# Display.net
KiCad netlist of a schematic drawn in EAGLE
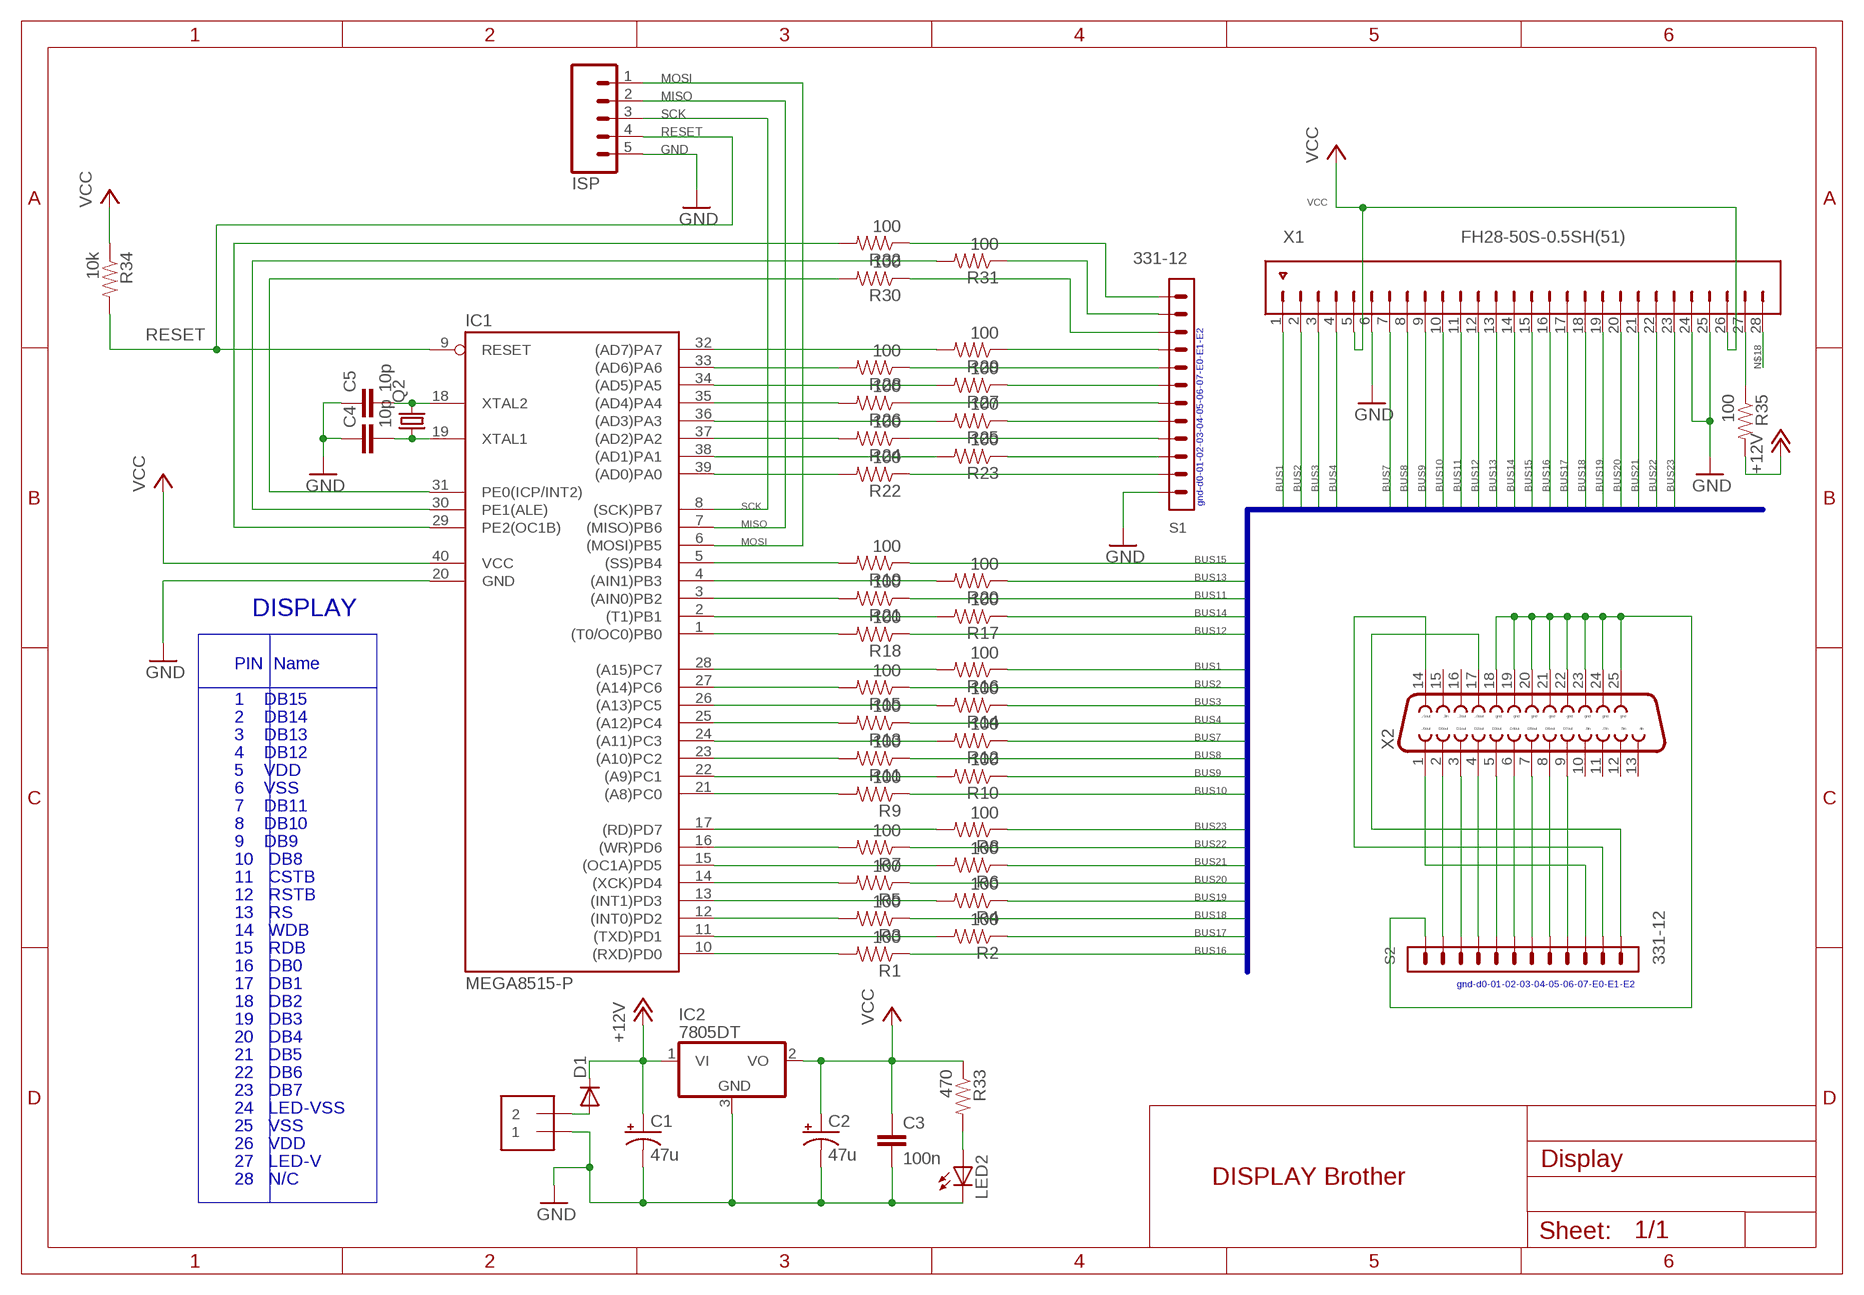
[diagram p0: schematic, sheet 1]

(export (version "E")
  (design (tool "Eeschema 10.0.6"))
  (components
    (comp (ref "C1")
      (value "47u")
      (footprint "eagle-import:EIA3216-KIT")
      (libsource (lib "eagle-import") (part "CAP_POL1206-KIT"))
    )
    (comp (ref "C2")
      (value "47u")
      (footprint "eagle-import:EIA3216-KIT")
      (libsource (lib "eagle-import") (part "CAP_POL1206-KIT"))
    )
    (comp (ref "C3")
      (value "100n")
      (footprint "eagle-import:0805")
      (libsource (lib "eagle-import") (part "CAP0805"))
    )
    (comp (ref "C4")
      (value "10p")
      (footprint "eagle-import:0805")
      (libsource (lib "eagle-import") (part "CAP0805"))
    )
    (comp (ref "C5")
      (value "10p")
      (footprint "eagle-import:0805")
      (libsource (lib "eagle-import") (part "CAP0805"))
    )
    (comp (ref "D1")
      (value "DIODESMA-KIT")
      (footprint "eagle-import:SMA-DIODE-KIT")
      (libsource (lib "eagle-import") (part "DIODESMA-KIT"))
    )
    (comp (ref "IC1")
      (value "MEGA8515-P")
      (footprint "eagle-import:DIL40")
      (fields (field (name "MPN") "ATMEGA8515-16PU"))
      (libsource (lib "eagle-import") (part "MEGA8515-P"))
    )
    (comp (ref "IC2")
      (value "7805DT")
      (footprint "eagle-import:TO252")
      (libsource (lib "eagle-import") (part "78DT05"))
    )
    (comp (ref "ISP")
      (value "M05PTH_LONGPADS")
      (footprint "eagle-import:1X05_LONGPADS")
      (libsource (lib "eagle-import") (part "M05PTH_LONGPADS"))
    )
    (comp (ref "J2")
      (value "1X2-3.5MM")
      (footprint "eagle-import:1X2-3.5MM")
      (libsource (lib "eagle-import") (part "1X2-3.5MM"))
    )
    (comp (ref "LED2")
      (value "LED3MM")
      (footprint "eagle-import:LED3MM")
      (libsource (lib "eagle-import") (part "LED3MM"))
    )
    (comp (ref "Q2")
      (value "CRYSTALHC49UP")
      (footprint "eagle-import:HC49UP")
      (fields (field (name "OC_FARNELL") "unknown"))
      (libsource (lib "eagle-import") (part "CRYSTALHC49UP"))
    )
    (comp (ref "R1")
      (value "100")
      (footprint "eagle-import:0805")
      (libsource (lib "eagle-import") (part "RESISTOR0805-RES"))
    )
    (comp (ref "R2")
      (value "100")
      (footprint "eagle-import:0805")
      (libsource (lib "eagle-import") (part "RESISTOR0805-RES"))
    )
    (comp (ref "R3")
      (value "100")
      (footprint "eagle-import:0805")
      (libsource (lib "eagle-import") (part "RESISTOR0805-RES"))
    )
    (comp (ref "R4")
      (value "100")
      (footprint "eagle-import:0805")
      (libsource (lib "eagle-import") (part "RESISTOR0805-RES"))
    )
    (comp (ref "R5")
      (value "100")
      (footprint "eagle-import:0805")
      (libsource (lib "eagle-import") (part "RESISTOR0805-RES"))
    )
    (comp (ref "R6")
      (value "100")
      (footprint "eagle-import:0805")
      (libsource (lib "eagle-import") (part "RESISTOR0805-RES"))
    )
    (comp (ref "R7")
      (value "100")
      (footprint "eagle-import:0805")
      (libsource (lib "eagle-import") (part "RESISTOR0805-RES"))
    )
    (comp (ref "R8")
      (value "100")
      (footprint "eagle-import:0805")
      (libsource (lib "eagle-import") (part "RESISTOR0805-RES"))
    )
    (comp (ref "R9")
      (value "100")
      (footprint "eagle-import:0805")
      (libsource (lib "eagle-import") (part "RESISTOR0805-RES"))
    )
    (comp (ref "R10")
      (value "100")
      (footprint "eagle-import:0805")
      (libsource (lib "eagle-import") (part "RESISTOR0805-RES"))
    )
    (comp (ref "R11")
      (value "100")
      (footprint "eagle-import:0805")
      (libsource (lib "eagle-import") (part "RESISTOR0805-RES"))
    )
    (comp (ref "R12")
      (value "100")
      (footprint "eagle-import:0805")
      (libsource (lib "eagle-import") (part "RESISTOR0805-RES"))
    )
    (comp (ref "R13")
      (value "100")
      (footprint "eagle-import:0805")
      (libsource (lib "eagle-import") (part "RESISTOR0805-RES"))
    )
    (comp (ref "R14")
      (value "100")
      (footprint "eagle-import:0805")
      (libsource (lib "eagle-import") (part "RESISTOR0805-RES"))
    )
    (comp (ref "R15")
      (value "100")
      (footprint "eagle-import:0805")
      (libsource (lib "eagle-import") (part "RESISTOR0805-RES"))
    )
    (comp (ref "R16")
      (value "100")
      (footprint "eagle-import:0805")
      (libsource (lib "eagle-import") (part "RESISTOR0805-RES"))
    )
    (comp (ref "R17")
      (value "100")
      (footprint "eagle-import:0805")
      (libsource (lib "eagle-import") (part "RESISTOR0805-RES"))
    )
    (comp (ref "R18")
      (value "100")
      (footprint "eagle-import:0805")
      (libsource (lib "eagle-import") (part "RESISTOR0805-RES"))
    )
    (comp (ref "R19")
      (value "100")
      (footprint "eagle-import:0805")
      (libsource (lib "eagle-import") (part "RESISTOR0805-RES"))
    )
    (comp (ref "R20")
      (value "100")
      (footprint "eagle-import:0805")
      (libsource (lib "eagle-import") (part "RESISTOR0805-RES"))
    )
    (comp (ref "R21")
      (value "100")
      (footprint "eagle-import:0805")
      (libsource (lib "eagle-import") (part "RESISTOR0805-RES"))
    )
    (comp (ref "R22")
      (value "100")
      (footprint "eagle-import:0805")
      (libsource (lib "eagle-import") (part "RESISTOR0805-RES"))
    )
    (comp (ref "R23")
      (value "100")
      (footprint "eagle-import:0805")
      (libsource (lib "eagle-import") (part "RESISTOR0805-RES"))
    )
    (comp (ref "R24")
      (value "100")
      (footprint "eagle-import:0805")
      (libsource (lib "eagle-import") (part "RESISTOR0805-RES"))
    )
    (comp (ref "R25")
      (value "100")
      (footprint "eagle-import:0805")
      (libsource (lib "eagle-import") (part "RESISTOR0805-RES"))
    )
    (comp (ref "R26")
      (value "100")
      (footprint "eagle-import:0805")
      (libsource (lib "eagle-import") (part "RESISTOR0805-RES"))
    )
    (comp (ref "R27")
      (value "100")
      (footprint "eagle-import:0805")
      (libsource (lib "eagle-import") (part "RESISTOR0805-RES"))
    )
    (comp (ref "R28")
      (value "100")
      (footprint "eagle-import:0805")
      (libsource (lib "eagle-import") (part "RESISTOR0805-RES"))
    )
    (comp (ref "R29")
      (value "100")
      (footprint "eagle-import:0805")
      (libsource (lib "eagle-import") (part "RESISTOR0805-RES"))
    )
    (comp (ref "R30")
      (value "100")
      (footprint "eagle-import:0805")
      (libsource (lib "eagle-import") (part "RESISTOR0805-RES"))
    )
    (comp (ref "R31")
      (value "100")
      (footprint "eagle-import:0805")
      (libsource (lib "eagle-import") (part "RESISTOR0805-RES"))
    )
    (comp (ref "R32")
      (value "100")
      (footprint "eagle-import:0805")
      (libsource (lib "eagle-import") (part "RESISTOR0805-RES"))
    )
    (comp (ref "R33")
      (value "470")
      (footprint "eagle-import:0805")
      (libsource (lib "eagle-import") (part "RESISTOR0805-RES"))
    )
    (comp (ref "R34")
      (value "10k")
      (footprint "eagle-import:0805")
      (libsource (lib "eagle-import") (part "RESISTOR0805-RES"))
    )
    (comp (ref "R35")
      (value "100")
      (footprint "eagle-import:0805")
      (libsource (lib "eagle-import") (part "RESISTOR0805-RES"))
    )
    (comp (ref "S1")
      (value "331-12")
      (footprint "eagle-import:331-12")
      (libsource (lib "eagle-import") (part "331-12"))
    )
    (comp (ref "S2")
      (value "331-12")
      (footprint "eagle-import:331-12")
      (libsource (lib "eagle-import") (part "331-12"))
    )
    (comp (ref "X1")
      (value "FH28-50S-0.5SH(51)")
      (footprint "eagle-import:FH28-50S-0.5SH(51)")
      (libsource (lib "eagle-import") (part "FH28-50S-0.5SH(51)"))
    )
    (comp (ref "X2")
      (value "F25D")
      (footprint "eagle-import:F25D")
      (libsource (lib "eagle-import") (part "F25D"))
    )
  )
  (nets
    (net (code "2") (name "+12V") (class "Default")
      (node (ref "C1") (pin "A") (pinfunction "+_A") (pintype "passive"))
      (node (ref "D1") (pin "C") (pinfunction "C_C") (pintype "passive"))
      (node (ref "IC2") (pin "1") (pinfunction "VI_1") (pintype "input"))
      (node (ref "R35") (pin "2") (pinfunction "2_2") (pintype "passive"))
    )
    (net (code "3") (name "/BUS1") (class "Default")
      (node (ref "R16") (pin "1") (pinfunction "1_1") (pintype "passive"))
      (node (ref "X1") (pin "1") (pinfunction "1_1") (pintype "passive"))
    )
    (net (code "4") (name "/BUS2") (class "Default")
      (node (ref "R15") (pin "1") (pinfunction "1_1") (pintype "passive"))
      (node (ref "X1") (pin "2") (pinfunction "2_2") (pintype "passive"))
    )
    (net (code "5") (name "/BUS3") (class "Default")
      (node (ref "R14") (pin "1") (pinfunction "1_1") (pintype "passive"))
      (node (ref "X1") (pin "3") (pinfunction "3_3") (pintype "passive"))
    )
    (net (code "6") (name "/BUS4") (class "Default")
      (node (ref "R13") (pin "1") (pinfunction "1_1") (pintype "passive"))
      (node (ref "X1") (pin "4") (pinfunction "4_4") (pintype "passive"))
    )
    (net (code "7") (name "/BUS7") (class "Default")
      (node (ref "R12") (pin "1") (pinfunction "1_1") (pintype "passive"))
      (node (ref "X1") (pin "7") (pinfunction "7_7") (pintype "passive"))
    )
    (net (code "8") (name "/BUS8") (class "Default")
      (node (ref "R11") (pin "1") (pinfunction "1_1") (pintype "passive"))
      (node (ref "X1") (pin "8") (pinfunction "8_8") (pintype "passive"))
    )
    (net (code "9") (name "/BUS9") (class "Default")
      (node (ref "R10") (pin "1") (pinfunction "1_1") (pintype "passive"))
      (node (ref "X1") (pin "9") (pinfunction "9_9") (pintype "passive"))
    )
    (net (code "10") (name "/BUS10") (class "Default")
      (node (ref "R9") (pin "1") (pinfunction "1_1") (pintype "passive"))
      (node (ref "X1") (pin "10") (pinfunction "10_10") (pintype "passive"))
    )
    (net (code "11") (name "/BUS11") (class "Default")
      (node (ref "R21") (pin "1") (pinfunction "1_1") (pintype "passive"))
      (node (ref "X1") (pin "11") (pinfunction "11_11") (pintype "passive"))
    )
    (net (code "12") (name "/BUS12") (class "Default")
      (node (ref "R18") (pin "1") (pinfunction "1_1") (pintype "passive"))
      (node (ref "X1") (pin "12") (pinfunction "12_12") (pintype "passive"))
    )
    (net (code "13") (name "/BUS13") (class "Default")
      (node (ref "R20") (pin "1") (pinfunction "1_1") (pintype "passive"))
      (node (ref "X1") (pin "13") (pinfunction "13_13") (pintype "passive"))
    )
    (net (code "14") (name "/BUS14") (class "Default")
      (node (ref "R17") (pin "1") (pinfunction "1_1") (pintype "passive"))
      (node (ref "X1") (pin "14") (pinfunction "14_14") (pintype "passive"))
    )
    (net (code "15") (name "/BUS15") (class "Default")
      (node (ref "R19") (pin "1") (pinfunction "1_1") (pintype "passive"))
      (node (ref "X1") (pin "15") (pinfunction "15_15") (pintype "passive"))
    )
    (net (code "16") (name "/BUS16") (class "Default")
      (node (ref "R1") (pin "1") (pinfunction "1_1") (pintype "passive"))
      (node (ref "X1") (pin "16") (pinfunction "16_16") (pintype "passive"))
    )
    (net (code "17") (name "/BUS17") (class "Default")
      (node (ref "R2") (pin "1") (pinfunction "1_1") (pintype "passive"))
      (node (ref "X1") (pin "17") (pinfunction "17_17") (pintype "passive"))
    )
    (net (code "18") (name "/BUS18") (class "Default")
      (node (ref "R3") (pin "1") (pinfunction "1_1") (pintype "passive"))
      (node (ref "X1") (pin "18") (pinfunction "18_18") (pintype "passive"))
    )
    (net (code "19") (name "/BUS19") (class "Default")
      (node (ref "R4") (pin "1") (pinfunction "1_1") (pintype "passive"))
      (node (ref "X1") (pin "19") (pinfunction "19_19") (pintype "passive"))
    )
    (net (code "20") (name "/BUS20") (class "Default")
      (node (ref "R5") (pin "1") (pinfunction "1_1") (pintype "passive"))
      (node (ref "X1") (pin "20") (pinfunction "20_20") (pintype "passive"))
    )
    (net (code "21") (name "/BUS21") (class "Default")
      (node (ref "R6") (pin "1") (pinfunction "1_1") (pintype "passive"))
      (node (ref "X1") (pin "21") (pinfunction "21_21") (pintype "passive"))
    )
    (net (code "22") (name "/BUS22") (class "Default")
      (node (ref "R7") (pin "1") (pinfunction "1_1") (pintype "passive"))
      (node (ref "X1") (pin "22") (pinfunction "22_22") (pintype "passive"))
    )
    (net (code "23") (name "/BUS23") (class "Default")
      (node (ref "R8") (pin "1") (pinfunction "1_1") (pintype "passive"))
      (node (ref "X1") (pin "23") (pinfunction "23_23") (pintype "passive"))
    )
    (net (code "24") (name "/MISO") (class "Default")
      (node (ref "IC1") (pin "7") (pinfunction "(MISO)PB6_7") (pintype "bidirectional"))
      (node (ref "ISP") (pin "2") (pinfunction "2_2") (pintype "passive"))
    )
    (net (code "25") (name "/MOSI") (class "Default")
      (node (ref "IC1") (pin "6") (pinfunction "(MOSI)PB5_6") (pintype "bidirectional"))
      (node (ref "ISP") (pin "1") (pinfunction "1_1") (pintype "passive"))
    )
    (net (code "26") (name "/N$18") (class "Default")
      (node (ref "X1") (pin "28") (pinfunction "28_28") (pintype "passive"))
    )
    (net (code "27") (name "/RESET") (class "Default")
      (node (ref "IC1") (pin "9") (pinfunction "RESET_9") (pintype "input"))
      (node (ref "ISP") (pin "4") (pinfunction "4_4") (pintype "passive"))
      (node (ref "R34") (pin "2") (pinfunction "2_2") (pintype "passive"))
    )
    (net (code "28") (name "/SCK") (class "Default")
      (node (ref "IC1") (pin "8") (pinfunction "(SCK)PB7_8") (pintype "bidirectional"))
      (node (ref "ISP") (pin "3") (pinfunction "3_3") (pintype "passive"))
    )
    (net (code "30") (name "GND") (class "Default")
      (node (ref "C1") (pin "C") (pinfunction "-_C") (pintype "passive"))
      (node (ref "C2") (pin "C") (pinfunction "-_C") (pintype "passive"))
      (node (ref "C3") (pin "2") (pinfunction "2_2") (pintype "passive"))
      (node (ref "C4") (pin "1") (pinfunction "1_1") (pintype "passive"))
      (node (ref "C5") (pin "1") (pinfunction "1_1") (pintype "passive"))
      (node (ref "IC1") (pin "20") (pinfunction "GND_20") (pintype "power_in"))
      (node (ref "IC2") (pin "3") (pinfunction "GND_3") (pintype "passive"))
      (node (ref "ISP") (pin "5") (pinfunction "5_5") (pintype "passive"))
      (node (ref "J2") (pin "1") (pinfunction "1_1") (pintype "passive"))
      (node (ref "LED2") (pin "K") (pinfunction "C_K") (pintype "passive"))
      (node (ref "S1") (pin "1") (pinfunction "1_1") (pintype "passive"))
      (node (ref "X1") (pin "24") (pinfunction "24_24") (pintype "passive"))
      (node (ref "X1") (pin "25") (pinfunction "25_25") (pintype "passive"))
      (node (ref "X1") (pin "6") (pinfunction "6_6") (pintype "passive"))
    )
    (net (code "31") (name "Net-(D1-PadA)") (class "Default")
      (node (ref "D1") (pin "A") (pinfunction "A_A") (pintype "passive"))
      (node (ref "J2") (pin "2") (pinfunction "2_2") (pintype "passive"))
    )
    (net (code "32") (name "Net-(IC1-(A8)PC0)") (class "Default")
      (node (ref "IC1") (pin "21") (pinfunction "(A8)PC0_21") (pintype "bidirectional"))
      (node (ref "R9") (pin "2") (pinfunction "2_2") (pintype "passive"))
    )
    (net (code "33") (name "Net-(IC1-(A9)PC1)") (class "Default")
      (node (ref "IC1") (pin "22") (pinfunction "(A9)PC1_22") (pintype "bidirectional"))
      (node (ref "R10") (pin "2") (pinfunction "2_2") (pintype "passive"))
    )
    (net (code "34") (name "Net-(IC1-(A10)PC2)") (class "Default")
      (node (ref "IC1") (pin "23") (pinfunction "(A10)PC2_23") (pintype "bidirectional"))
      (node (ref "R11") (pin "2") (pinfunction "2_2") (pintype "passive"))
    )
    (net (code "35") (name "Net-(IC1-(A11)PC3)") (class "Default")
      (node (ref "IC1") (pin "24") (pinfunction "(A11)PC3_24") (pintype "bidirectional"))
      (node (ref "R12") (pin "2") (pinfunction "2_2") (pintype "passive"))
    )
    (net (code "36") (name "Net-(IC1-(A12)PC4)") (class "Default")
      (node (ref "IC1") (pin "25") (pinfunction "(A12)PC4_25") (pintype "bidirectional"))
      (node (ref "R13") (pin "2") (pinfunction "2_2") (pintype "passive"))
    )
    (net (code "37") (name "Net-(IC1-(A13)PC5)") (class "Default")
      (node (ref "IC1") (pin "26") (pinfunction "(A13)PC5_26") (pintype "bidirectional"))
      (node (ref "R14") (pin "2") (pinfunction "2_2") (pintype "passive"))
    )
    (net (code "38") (name "Net-(IC1-(A14)PC6)") (class "Default")
      (node (ref "IC1") (pin "27") (pinfunction "(A14)PC6_27") (pintype "bidirectional"))
      (node (ref "R15") (pin "2") (pinfunction "2_2") (pintype "passive"))
    )
    (net (code "39") (name "Net-(IC1-(A15)PC7)") (class "Default")
      (node (ref "IC1") (pin "28") (pinfunction "(A15)PC7_28") (pintype "bidirectional"))
      (node (ref "R16") (pin "2") (pinfunction "2_2") (pintype "passive"))
    )
    (net (code "40") (name "Net-(IC1-(AD0)PA0)") (class "Default")
      (node (ref "IC1") (pin "39") (pinfunction "(AD0)PA0_39") (pintype "bidirectional"))
      (node (ref "R22") (pin "2") (pinfunction "2_2") (pintype "passive"))
    )
    (net (code "41") (name "Net-(IC1-(AD1)PA1)") (class "Default")
      (node (ref "IC1") (pin "38") (pinfunction "(AD1)PA1_38") (pintype "bidirectional"))
      (node (ref "R23") (pin "2") (pinfunction "2_2") (pintype "passive"))
    )
    (net (code "42") (name "Net-(IC1-(AD2)PA2)") (class "Default")
      (node (ref "IC1") (pin "37") (pinfunction "(AD2)PA2_37") (pintype "bidirectional"))
      (node (ref "R24") (pin "2") (pinfunction "2_2") (pintype "passive"))
    )
    (net (code "43") (name "Net-(IC1-(AD3)PA3)") (class "Default")
      (node (ref "IC1") (pin "36") (pinfunction "(AD3)PA3_36") (pintype "bidirectional"))
      (node (ref "R25") (pin "2") (pinfunction "2_2") (pintype "passive"))
    )
    (net (code "44") (name "Net-(IC1-(AD4)PA4)") (class "Default")
      (node (ref "IC1") (pin "35") (pinfunction "(AD4)PA4_35") (pintype "bidirectional"))
      (node (ref "R26") (pin "2") (pinfunction "2_2") (pintype "passive"))
    )
    (net (code "45") (name "Net-(IC1-(AD5)PA5)") (class "Default")
      (node (ref "IC1") (pin "34") (pinfunction "(AD5)PA5_34") (pintype "bidirectional"))
      (node (ref "R27") (pin "2") (pinfunction "2_2") (pintype "passive"))
    )
    (net (code "46") (name "Net-(IC1-(AD6)PA6)") (class "Default")
      (node (ref "IC1") (pin "33") (pinfunction "(AD6)PA6_33") (pintype "bidirectional"))
      (node (ref "R28") (pin "2") (pinfunction "2_2") (pintype "passive"))
    )
    (net (code "47") (name "Net-(IC1-(AD7)PA7)") (class "Default")
      (node (ref "IC1") (pin "32") (pinfunction "(AD7)PA7_32") (pintype "bidirectional"))
      (node (ref "R29") (pin "2") (pinfunction "2_2") (pintype "passive"))
    )
    (net (code "48") (name "Net-(IC1-(AIN0)PB2)") (class "Default")
      (node (ref "IC1") (pin "3") (pinfunction "(AIN0)PB2_3") (pintype "bidirectional"))
      (node (ref "R21") (pin "2") (pinfunction "2_2") (pintype "passive"))
    )
    (net (code "49") (name "Net-(IC1-(AIN1)PB3)") (class "Default")
      (node (ref "IC1") (pin "4") (pinfunction "(AIN1)PB3_4") (pintype "bidirectional"))
      (node (ref "R20") (pin "2") (pinfunction "2_2") (pintype "passive"))
    )
    (net (code "50") (name "Net-(IC1-(INT0)PD2)") (class "Default")
      (node (ref "IC1") (pin "12") (pinfunction "(INT0)PD2_12") (pintype "bidirectional"))
      (node (ref "R3") (pin "2") (pinfunction "2_2") (pintype "passive"))
    )
    (net (code "51") (name "Net-(IC1-(INT1)PD3)") (class "Default")
      (node (ref "IC1") (pin "13") (pinfunction "(INT1)PD3_13") (pintype "bidirectional"))
      (node (ref "R4") (pin "2") (pinfunction "2_2") (pintype "passive"))
    )
    (net (code "52") (name "Net-(IC1-(OC1A)PD5)") (class "Default")
      (node (ref "IC1") (pin "15") (pinfunction "(OC1A)PD5_15") (pintype "bidirectional"))
      (node (ref "R6") (pin "2") (pinfunction "2_2") (pintype "passive"))
    )
    (net (code "53") (name "Net-(IC1-(RD)PD7)") (class "Default")
      (node (ref "IC1") (pin "17") (pinfunction "(RD)PD7_17") (pintype "bidirectional"))
      (node (ref "R8") (pin "2") (pinfunction "2_2") (pintype "passive"))
    )
    (net (code "54") (name "Net-(IC1-(RXD)PD0)") (class "Default")
      (node (ref "IC1") (pin "10") (pinfunction "(RXD)PD0_10") (pintype "bidirectional"))
      (node (ref "R1") (pin "2") (pinfunction "2_2") (pintype "passive"))
    )
    (net (code "55") (name "Net-(IC1-(SS)PB4)") (class "Default")
      (node (ref "IC1") (pin "5") (pinfunction "(SS)PB4_5") (pintype "bidirectional"))
      (node (ref "R19") (pin "2") (pinfunction "2_2") (pintype "passive"))
    )
    (net (code "56") (name "Net-(IC1-(T0{slash}OC0)PB0)") (class "Default")
      (node (ref "IC1") (pin "1") (pinfunction "(T0/OC0)PB0_1") (pintype "bidirectional"))
      (node (ref "R18") (pin "2") (pinfunction "2_2") (pintype "passive"))
    )
    (net (code "57") (name "Net-(IC1-(T1)PB1)") (class "Default")
      (node (ref "IC1") (pin "2") (pinfunction "(T1)PB1_2") (pintype "bidirectional"))
      (node (ref "R17") (pin "2") (pinfunction "2_2") (pintype "passive"))
    )
    (net (code "58") (name "Net-(IC1-(TXD)PD1)") (class "Default")
      (node (ref "IC1") (pin "11") (pinfunction "(TXD)PD1_11") (pintype "bidirectional"))
      (node (ref "R2") (pin "2") (pinfunction "2_2") (pintype "passive"))
    )
    (net (code "59") (name "Net-(IC1-(WR)PD6)") (class "Default")
      (node (ref "IC1") (pin "16") (pinfunction "(WR)PD6_16") (pintype "bidirectional"))
      (node (ref "R7") (pin "2") (pinfunction "2_2") (pintype "passive"))
    )
    (net (code "60") (name "Net-(IC1-(XCK)PD4)") (class "Default")
      (node (ref "IC1") (pin "14") (pinfunction "(XCK)PD4_14") (pintype "bidirectional"))
      (node (ref "R5") (pin "2") (pinfunction "2_2") (pintype "passive"))
    )
    (net (code "61") (name "Net-(IC1-PE0(ICP{slash}INT2))") (class "Default")
      (node (ref "IC1") (pin "31") (pinfunction "PE0(ICP/INT2)_31") (pintype "bidirectional"))
      (node (ref "R30") (pin "2") (pinfunction "2_2") (pintype "passive"))
    )
    (net (code "62") (name "Net-(IC1-PE1(ALE))") (class "Default")
      (node (ref "IC1") (pin "30") (pinfunction "PE1(ALE)_30") (pintype "bidirectional"))
      (node (ref "R31") (pin "2") (pinfunction "2_2") (pintype "passive"))
    )
    (net (code "63") (name "Net-(IC1-PE2(OC1B))") (class "Default")
      (node (ref "IC1") (pin "29") (pinfunction "PE2(OC1B)_29") (pintype "bidirectional"))
      (node (ref "R32") (pin "2") (pinfunction "2_2") (pintype "passive"))
    )
    (net (code "64") (name "Net-(IC1-XTAL1)") (class "Default")
      (node (ref "C4") (pin "2") (pinfunction "2_2") (pintype "passive"))
      (node (ref "IC1") (pin "19") (pinfunction "XTAL1_19") (pintype "bidirectional"))
      (node (ref "Q2") (pin "1") (pinfunction "1_1") (pintype "passive"))
    )
    (net (code "65") (name "Net-(IC1-XTAL2)") (class "Default")
      (node (ref "C5") (pin "2") (pinfunction "2_2") (pintype "passive"))
      (node (ref "IC1") (pin "18") (pinfunction "XTAL2_18") (pintype "bidirectional"))
      (node (ref "Q2") (pin "2") (pinfunction "2_2") (pintype "passive"))
    )
    (net (code "66") (name "Net-(LED2-PadA)") (class "Default")
      (node (ref "LED2") (pin "A") (pinfunction "A_A") (pintype "passive"))
      (node (ref "R33") (pin "2") (pinfunction "2_2") (pintype "passive"))
    )
    (net (code "67") (name "Net-(R22-Pad1)") (class "Default")
      (node (ref "R22") (pin "1") (pinfunction "1_1") (pintype "passive"))
      (node (ref "S1") (pin "2") (pinfunction "2_2") (pintype "passive"))
    )
    (net (code "68") (name "Net-(R23-Pad1)") (class "Default")
      (node (ref "R23") (pin "1") (pinfunction "1_1") (pintype "passive"))
      (node (ref "S1") (pin "3") (pinfunction "3_3") (pintype "passive"))
    )
    (net (code "69") (name "Net-(R24-Pad1)") (class "Default")
      (node (ref "R24") (pin "1") (pinfunction "1_1") (pintype "passive"))
      (node (ref "S1") (pin "4") (pinfunction "4_4") (pintype "passive"))
    )
    (net (code "70") (name "Net-(R25-Pad1)") (class "Default")
      (node (ref "R25") (pin "1") (pinfunction "1_1") (pintype "passive"))
      (node (ref "S1") (pin "5") (pinfunction "5_5") (pintype "passive"))
    )
    (net (code "71") (name "Net-(R26-Pad1)") (class "Default")
      (node (ref "R26") (pin "1") (pinfunction "1_1") (pintype "passive"))
      (node (ref "S1") (pin "6") (pinfunction "6_6") (pintype "passive"))
    )
    (net (code "72") (name "Net-(R27-Pad1)") (class "Default")
      (node (ref "R27") (pin "1") (pinfunction "1_1") (pintype "passive"))
      (node (ref "S1") (pin "7") (pinfunction "7_7") (pintype "passive"))
    )
    (net (code "73") (name "Net-(R28-Pad1)") (class "Default")
      (node (ref "R28") (pin "1") (pinfunction "1_1") (pintype "passive"))
      (node (ref "S1") (pin "8") (pinfunction "8_8") (pintype "passive"))
    )
    (net (code "74") (name "Net-(R29-Pad1)") (class "Default")
      (node (ref "R29") (pin "1") (pinfunction "1_1") (pintype "passive"))
      (node (ref "S1") (pin "9") (pinfunction "9_9") (pintype "passive"))
    )
    (net (code "75") (name "Net-(R30-Pad1)") (class "Default")
      (node (ref "R30") (pin "1") (pinfunction "1_1") (pintype "passive"))
      (node (ref "S1") (pin "10") (pinfunction "10_10") (pintype "passive"))
    )
    (net (code "76") (name "Net-(R31-Pad1)") (class "Default")
      (node (ref "R31") (pin "1") (pinfunction "1_1") (pintype "passive"))
      (node (ref "S1") (pin "11") (pinfunction "11_11") (pintype "passive"))
    )
    (net (code "77") (name "Net-(R32-Pad1)") (class "Default")
      (node (ref "R32") (pin "1") (pinfunction "1_1") (pintype "passive"))
      (node (ref "S1") (pin "12") (pinfunction "12_12") (pintype "passive"))
    )
    (net (code "78") (name "Net-(R35-Pad1)") (class "Default")
      (node (ref "R35") (pin "1") (pinfunction "1_1") (pintype "passive"))
      (node (ref "X1") (pin "27") (pinfunction "27_27") (pintype "passive"))
    )
    (net (code "79") (name "Net-(S2-Pad1)") (class "Default")
      (node (ref "S2") (pin "1") (pinfunction "1_1") (pintype "passive"))
      (node (ref "X2") (pin "18") (pinfunction "18_18") (pintype "passive"))
      (node (ref "X2") (pin "19") (pinfunction "19_19") (pintype "passive"))
      (node (ref "X2") (pin "20") (pinfunction "20_20") (pintype "passive"))
      (node (ref "X2") (pin "21") (pinfunction "21_21") (pintype "passive"))
      (node (ref "X2") (pin "22") (pinfunction "22_22") (pintype "passive"))
      (node (ref "X2") (pin "23") (pinfunction "23_23") (pintype "passive"))
      (node (ref "X2") (pin "24") (pinfunction "24_24") (pintype "passive"))
      (node (ref "X2") (pin "25") (pinfunction "25_25") (pintype "passive"))
    )
    (net (code "80") (name "Net-(S2-Pad2)") (class "Default")
      (node (ref "S2") (pin "2") (pinfunction "2_2") (pintype "passive"))
      (node (ref "X2") (pin "2") (pinfunction "2_2") (pintype "passive"))
    )
    (net (code "81") (name "Net-(S2-Pad3)") (class "Default")
      (node (ref "S2") (pin "3") (pinfunction "3_3") (pintype "passive"))
      (node (ref "X2") (pin "3") (pinfunction "3_3") (pintype "passive"))
    )
    (net (code "82") (name "Net-(S2-Pad4)") (class "Default")
      (node (ref "S2") (pin "4") (pinfunction "4_4") (pintype "passive"))
      (node (ref "X2") (pin "4") (pinfunction "4_4") (pintype "passive"))
    )
    (net (code "83") (name "Net-(S2-Pad5)") (class "Default")
      (node (ref "S2") (pin "5") (pinfunction "5_5") (pintype "passive"))
      (node (ref "X2") (pin "5") (pinfunction "5_5") (pintype "passive"))
    )
    (net (code "84") (name "Net-(S2-Pad6)") (class "Default")
      (node (ref "S2") (pin "6") (pinfunction "6_6") (pintype "passive"))
      (node (ref "X2") (pin "6") (pinfunction "6_6") (pintype "passive"))
    )
    (net (code "85") (name "Net-(S2-Pad7)") (class "Default")
      (node (ref "S2") (pin "7") (pinfunction "7_7") (pintype "passive"))
      (node (ref "X2") (pin "7") (pinfunction "7_7") (pintype "passive"))
    )
    (net (code "86") (name "Net-(S2-Pad8)") (class "Default")
      (node (ref "S2") (pin "8") (pinfunction "8_8") (pintype "passive"))
      (node (ref "X2") (pin "8") (pinfunction "8_8") (pintype "passive"))
    )
    (net (code "87") (name "Net-(S2-Pad9)") (class "Default")
      (node (ref "S2") (pin "9") (pinfunction "9_9") (pintype "passive"))
      (node (ref "X2") (pin "9") (pinfunction "9_9") (pintype "passive"))
    )
    (net (code "88") (name "Net-(S2-Pad10)") (class "Default")
      (node (ref "S2") (pin "10") (pinfunction "10_10") (pintype "passive"))
      (node (ref "X2") (pin "1") (pinfunction "1_1") (pintype "passive"))
    )
    (net (code "89") (name "Net-(S2-Pad11)") (class "Default")
      (node (ref "S2") (pin "11") (pinfunction "11_11") (pintype "passive"))
      (node (ref "X2") (pin "14") (pinfunction "14_14") (pintype "passive"))
    )
    (net (code "90") (name "Net-(S2-Pad12)") (class "Default")
      (node (ref "S2") (pin "12") (pinfunction "12_12") (pintype "passive"))
      (node (ref "X2") (pin "17") (pinfunction "17_17") (pintype "passive"))
    )
    (net (code "91") (name "VCC") (class "Default")
      (node (ref "C2") (pin "A") (pinfunction "+_A") (pintype "passive"))
      (node (ref "C3") (pin "1") (pinfunction "1_1") (pintype "passive"))
      (node (ref "IC1") (pin "40") (pinfunction "VCC_40") (pintype "power_in"))
      (node (ref "IC2") (pin "2") (pinfunction "VO_2") (pintype "passive"))
      (node (ref "R33") (pin "1") (pinfunction "1_1") (pintype "passive"))
      (node (ref "R34") (pin "1") (pinfunction "1_1") (pintype "passive"))
      (node (ref "X1") (pin "26") (pinfunction "26_26") (pintype "passive"))
      (node (ref "X1") (pin "5") (pinfunction "5_5") (pintype "passive"))
    )
    (net (code "92") (name "unconnected-(X2-Pad10)") (class "Default")
      (node (ref "X2") (pin "10") (pinfunction "10_10") (pintype "passive"))
    )
    (net (code "93") (name "unconnected-(X2-Pad11)") (class "Default")
      (node (ref "X2") (pin "11") (pinfunction "11_11") (pintype "passive"))
    )
    (net (code "94") (name "unconnected-(X2-Pad12)") (class "Default")
      (node (ref "X2") (pin "12") (pinfunction "12_12") (pintype "passive"))
    )
    (net (code "95") (name "unconnected-(X2-Pad13)") (class "Default")
      (node (ref "X2") (pin "13") (pinfunction "13_13") (pintype "passive"))
    )
    (net (code "96") (name "unconnected-(X2-Pad15)") (class "Default")
      (node (ref "X2") (pin "15") (pinfunction "15_15") (pintype "passive"))
    )
    (net (code "97") (name "unconnected-(X2-Pad16)") (class "Default")
      (node (ref "X2") (pin "16") (pinfunction "16_16") (pintype "passive"))
    )
  )
)
